# Power_Supply.net
KiCad netlist of a schematic drawn in Altium Designer
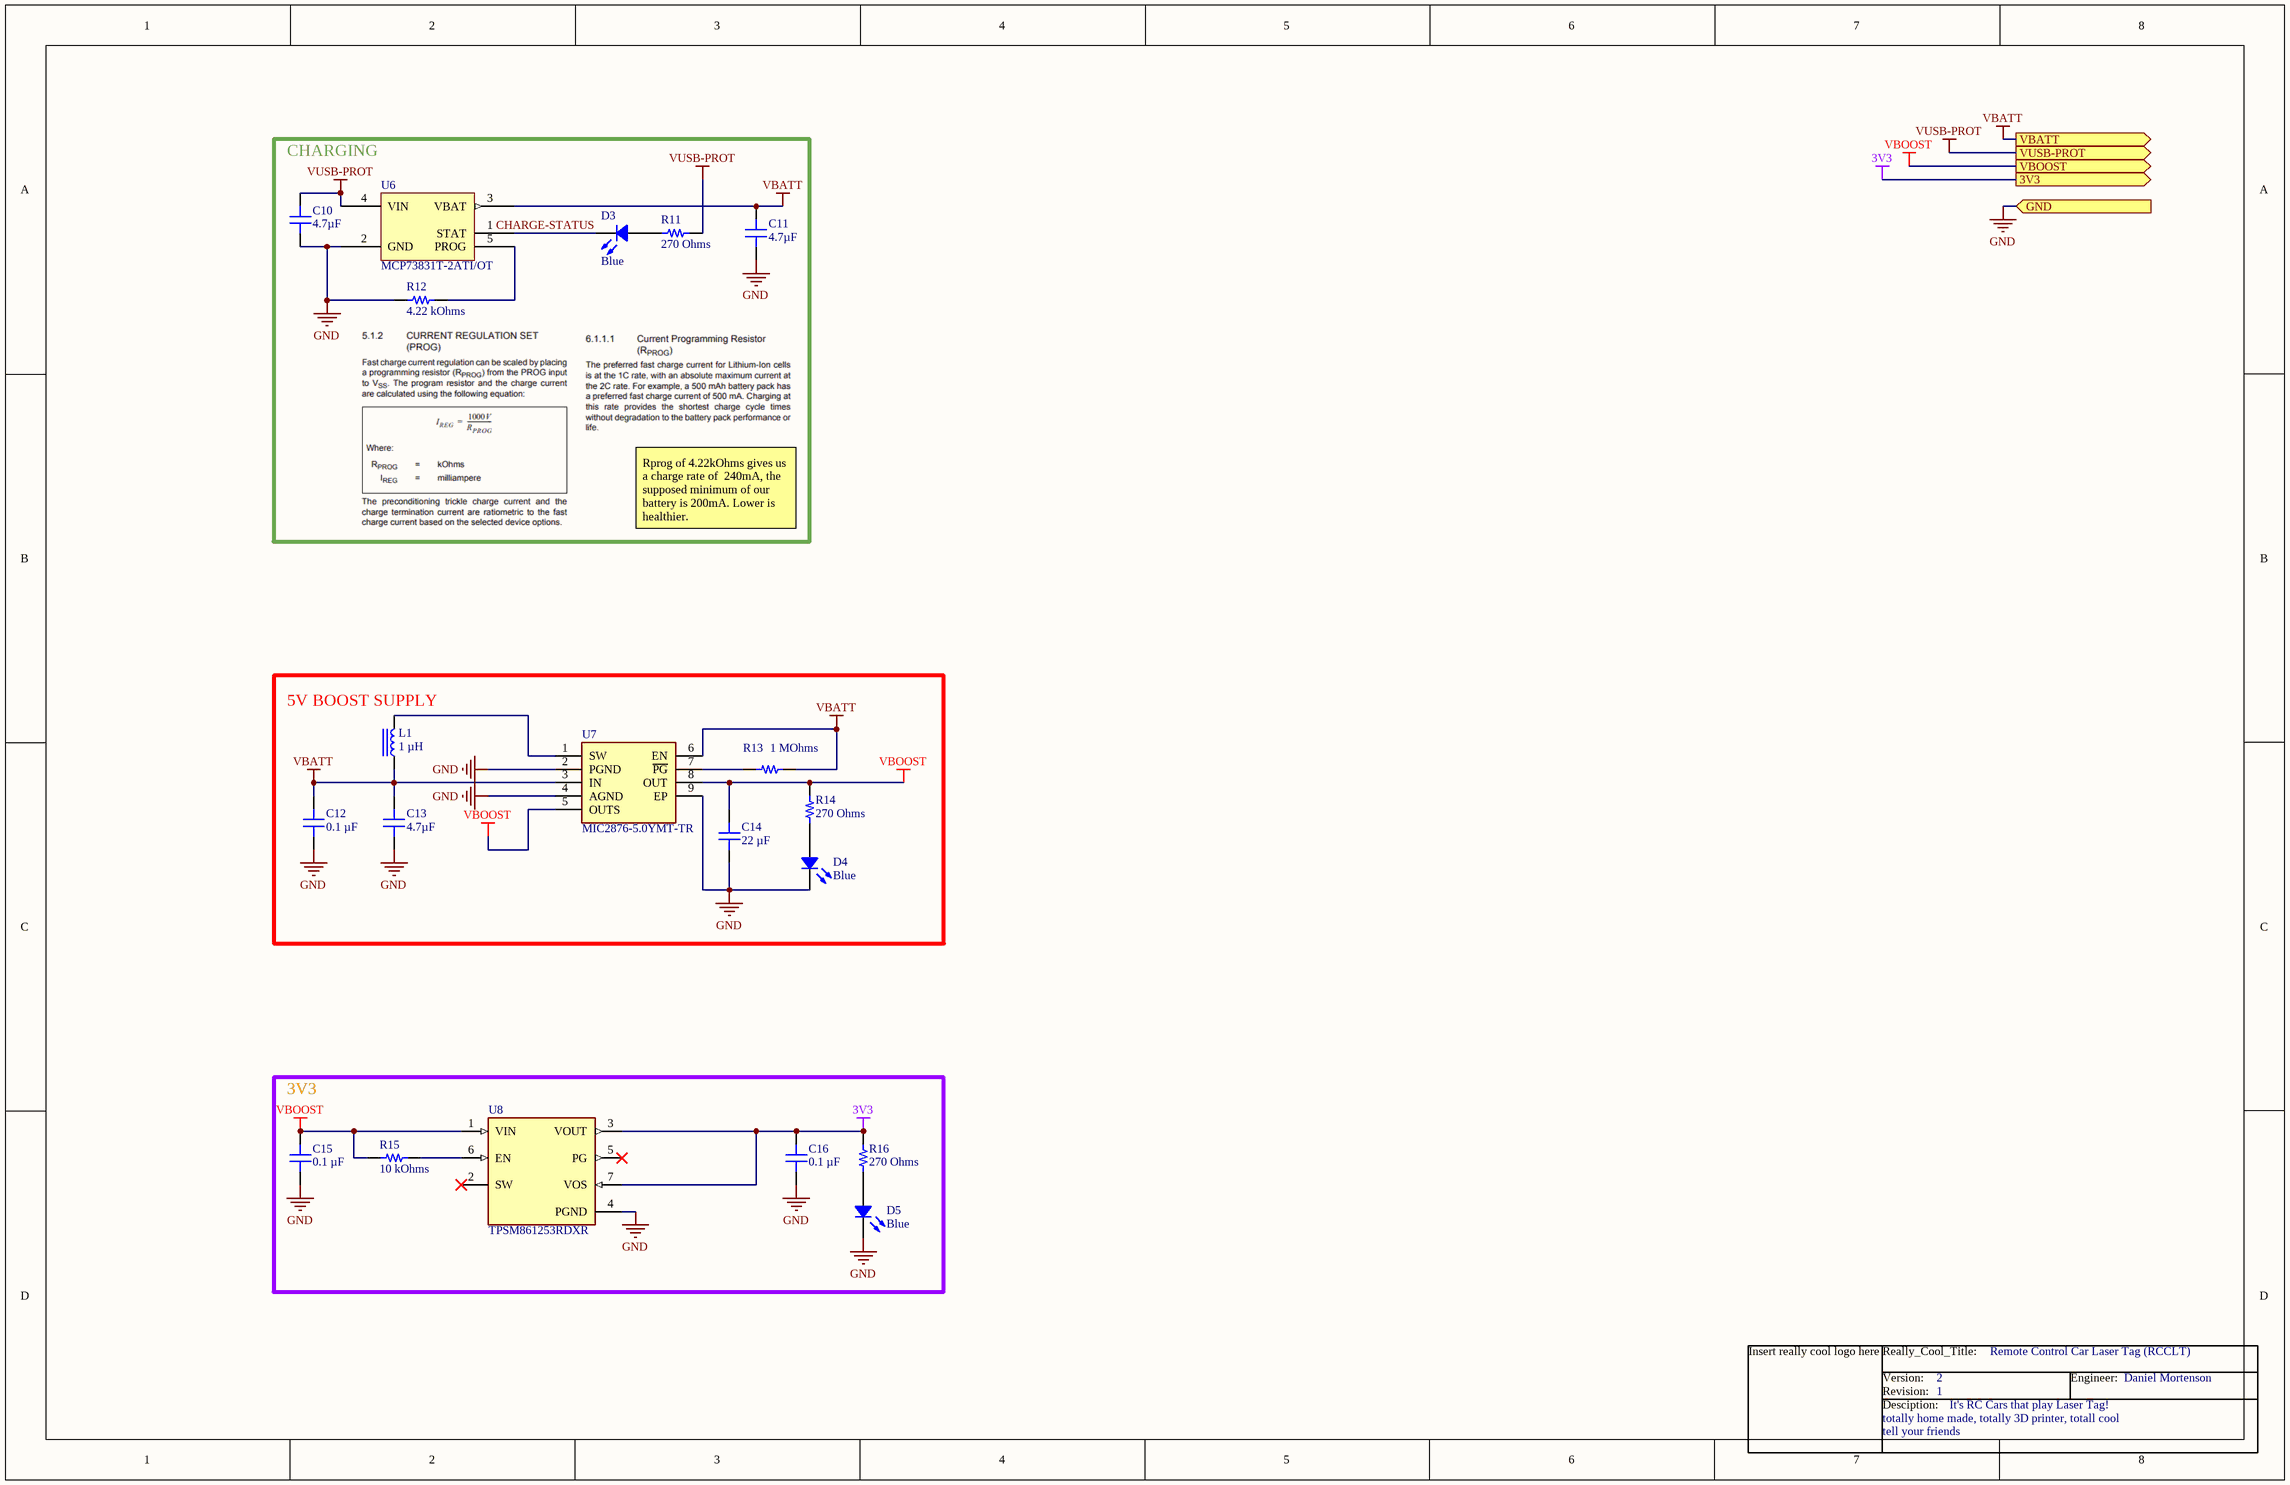
[diagram p0: Power_Supply.SchDoc]

(export (version "E")
  (design (tool "Eeschema 10.0.6"))
  (components
    (comp (ref "C10")
      (value "4.7µF")
      (footprint "CAP 0805_2012")
      (description "CAP CER 4.7UF 16V X7R 0805")
      (fields
        (field (name "PART NUMBER") "0805YC475KAT2A")
        (field (name "CAPACITANCE") "4.7µF")
        (field (name "MANUFACTURER") "AVX Corporation")
      )
      (libsource (lib "dblib") (part "Capacitor"))
    )
    (comp (ref "C11")
      (value "4.7µF")
      (footprint "CAP 0805_2012")
      (description "CAP CER 4.7UF 16V X7R 0805")
      (fields
        (field (name "PART NUMBER") "0805YC475KAT2A")
        (field (name "CAPACITANCE") "4.7µF")
        (field (name "MANUFACTURER") "AVX Corporation")
      )
      (libsource (lib "dblib") (part "Capacitor"))
    )
    (comp (ref "C12")
      (value "0.1 µF")
      (footprint "CAP 0805_2012")
      (description "CAP CER 0.1UF 25V X7R 0805")
      (fields
        (field (name "PART NUMBER") "0805B104K250CT")
        (field (name "CAPACITANCE") "0.1 µF")
        (field (name "MANUFACTURER") "Walsin Technology Corporation")
      )
      (libsource (lib "dblib") (part "Capacitor"))
    )
    (comp (ref "C13")
      (value "4.7µF")
      (footprint "CAP 0805_2012")
      (description "CAP CER 4.7UF 16V X7R 0805")
      (fields
        (field (name "PART NUMBER") "0805YC475KAT2A")
        (field (name "CAPACITANCE") "4.7µF")
        (field (name "MANUFACTURER") "AVX Corporation")
      )
      (libsource (lib "dblib") (part "Capacitor"))
    )
    (comp (ref "C14")
      (value "22 µF")
      (footprint "CAP 0805_2012")
      (description "CAP CER 22UF 6.3V X5R 0805")
      (fields
        (field (name "PART NUMBER") "CL21A226KQQNNNE")
        (field (name "CAPACITANCE") "22 µF")
        (field (name "MANUFACTURER") "Samsung Electro-Mechanics")
      )
      (libsource (lib "dblib") (part "Capacitor"))
    )
    (comp (ref "C15")
      (value "0.1 µF")
      (footprint "CAP 0805_2012")
      (description "CAP CER 0.1UF 25V X7R 0805")
      (fields
        (field (name "PART NUMBER") "0805B104K250CT")
        (field (name "CAPACITANCE") "0.1 µF")
        (field (name "MANUFACTURER") "Walsin Technology Corporation")
      )
      (libsource (lib "dblib") (part "Capacitor"))
    )
    (comp (ref "C16")
      (value "0.1 µF")
      (footprint "CAP 0805_2012")
      (description "CAP CER 0.1UF 25V X7R 0805")
      (fields
        (field (name "PART NUMBER") "0805B104K250CT")
        (field (name "CAPACITANCE") "0.1 µF")
        (field (name "MANUFACTURER") "Walsin Technology Corporation")
      )
      (libsource (lib "dblib") (part "Capacitor"))
    )
    (comp (ref "D3")
      (value "Blue")
      (footprint "LED 0805_2012 BLUE")
      (description "LED BLUE CLEAR 0805 SMD")
      (fields (field (name "PART NUMBER") "150080BS75000") (field (name "MANUFACTURER") "Würth Elektronik"))
      (libsource (lib "dblib") (part "LED"))
    )
    (comp (ref "D4")
      (value "Blue")
      (footprint "LED 0805_2012 BLUE")
      (description "LED BLUE CLEAR 0805 SMD")
      (fields (field (name "PART NUMBER") "150080BS75000") (field (name "MANUFACTURER") "Würth Elektronik"))
      (libsource (lib "dblib") (part "LED"))
    )
    (comp (ref "D5")
      (value "Blue")
      (footprint "LED 0805_2012 BLUE")
      (description "LED BLUE CLEAR 0805 SMD")
      (fields (field (name "PART NUMBER") "150080BS75000") (field (name "MANUFACTURER") "Würth Elektronik"))
      (libsource (lib "dblib") (part "LED"))
    )
    (comp (ref "L1")
      (value "1 µH")
      (footprint "TAIYO YUDEN MAMK2520T1R0M")
      (description "FIXED IND 1UH 2.7A 59 MOHM SMD")
      (fields (field (name "PART NUMBER") "MAMK2520T1R0M") (field (name "MANUFACTURER") "Taiyo Yuden"))
      (libsource (lib "dblib") (part "Inductor"))
    )
    (comp (ref "R11")
      (value "270 Ohms")
      (footprint "RES 0805_2012")
      (description "RES SMD 270 OHM 1% 1/8W 0805")
      (fields
        (field (name "PART NUMBER") "CRG0805F270R")
        (field (name "MANUFACTURER") "TE Connectivity Passive Product")
      )
      (libsource (lib "dblib") (part "Resistor"))
    )
    (comp (ref "R12")
      (value "4.22 kOhms")
      (footprint "RES 0805_2012")
      (description "RES SMD 4.22K OHM 0.1% 1/8W 0805")
      (fields
        (field (name "PART NUMBER") "ERA-6AEB4221V")
        (field (name "MANUFACTURER") "Panasonic Electronic Components")
      )
      (libsource (lib "dblib") (part "Resistor"))
    )
    (comp (ref "R13")
      (value "1 MOhms")
      (footprint "RES 0805_2012")
      (description "RES 1M OHM 0.1% 1/8W 0805")
      (fields
        (field (name "PART NUMBER") "ERA-6AEB105V")
        (field (name "MANUFACTURER") "Panasonic Electronic Components")
      )
      (libsource (lib "dblib") (part "Resistor"))
    )
    (comp (ref "R14")
      (value "270 Ohms")
      (footprint "RES 0805_2012")
      (description "RES SMD 270 OHM 1% 1/8W 0805")
      (fields
        (field (name "PART NUMBER") "CRG0805F270R")
        (field (name "MANUFACTURER") "TE Connectivity Passive Product")
      )
      (libsource (lib "dblib") (part "Resistor"))
    )
    (comp (ref "R15")
      (value "10 kOhms")
      (footprint "RES 0805_2012")
      (description "RES SMD 10K OHM 1% 1/8W 0805")
      (fields (field (name "PART NUMBER") "CRCW080510K0FKEA") (field (name "MANUFACTURER") "Vishay Dale"))
      (libsource (lib "dblib") (part "Resistor"))
    )
    (comp (ref "R16")
      (value "270 Ohms")
      (footprint "RES 0805_2012")
      (description "RES SMD 270 OHM 1% 1/8W 0805")
      (fields
        (field (name "PART NUMBER") "CRG0805F270R")
        (field (name "MANUFACTURER") "TE Connectivity Passive Product")
      )
      (libsource (lib "dblib") (part "Resistor"))
    )
    (comp (ref "U6")
      (value "MCP73831T-2ATI/OT")
      (footprint "MICROCHIP SOT-23-5 OT")
      (description "IC CONTROLLR LI-ION 4.2V SOT23-5")
      (fields (field (name "MANUFACTURER") "Microchip Technology"))
      (libsource (lib "dblib") (part "MICROCHIP MCP73831"))
    )
    (comp (ref "U7")
      (value "MIC2876-5.0YMT-TR")
      (footprint "SamacSys:MIC287650YMTTR")
      (description "Integrated Circuit")
      (fields (field (name "MOUSER PART NUMBER") "998-MIC2876-50YMTTR"))
      (libsource (lib "*") (part "MIC2876-5.0YMT-TR"))
    )
    (comp (ref "U8")
      (value "TPSM861253RDXR")
      (footprint "VREG_TPSM861253RDXR")
      (description "3V to 17V input voltage, 3.3V, 1A output synchronous buck module in QFN package")
      (fields (field (name "MF") "Texas Instruments"))
      (libsource (lib "TPSM861253RDXR") (part "TPSM861253RDXR"))
    )
  )
  (nets
    (net (code "1") (name "/CHARGE-STATUS") (class "Default")
      (node (ref "D3") (pin "2") (pinfunction "2_2") (pintype "passive"))
      (node (ref "U6") (pin "1") (pinfunction "STAT_1") (pintype "passive"))
    )
    (net (code "2") (name "3V3") (class "Default")
      (node (ref "C16") (pin "2") (pinfunction "2_2") (pintype "passive"))
      (node (ref "R16") (pin "1") (pinfunction "1_1") (pintype "passive"))
      (node (ref "U8") (pin "3") (pinfunction "VOUT_3") (pintype "output"))
      (node (ref "U8") (pin "7") (pinfunction "VOS_7") (pintype "input"))
    )
    (net (code "3") (name "GND") (class "Default")
      (node (ref "C10") (pin "2") (pinfunction "2_2") (pintype "passive"))
      (node (ref "C11") (pin "2") (pinfunction "2_2") (pintype "passive"))
      (node (ref "C12") (pin "1") (pinfunction "1_1") (pintype "passive"))
      (node (ref "C13") (pin "1") (pinfunction "1_1") (pintype "passive"))
      (node (ref "C14") (pin "1") (pinfunction "1_1") (pintype "passive"))
      (node (ref "C15") (pin "1") (pinfunction "1_1") (pintype "passive"))
      (node (ref "C16") (pin "1") (pinfunction "1_1") (pintype "passive"))
      (node (ref "D4") (pin "2") (pinfunction "2_2") (pintype "passive"))
      (node (ref "D5") (pin "2") (pinfunction "2_2") (pintype "passive"))
      (node (ref "R12") (pin "1") (pinfunction "1_1") (pintype "passive"))
      (node (ref "U6") (pin "2") (pinfunction "GND_2") (pintype "passive"))
      (node (ref "U7") (pin "2") (pinfunction "PGND_2") (pintype "passive"))
      (node (ref "U7") (pin "4") (pinfunction "AGND_4") (pintype "passive"))
      (node (ref "U7") (pin "9") (pinfunction "EP_9") (pintype "passive"))
      (node (ref "U8") (pin "4") (pinfunction "PGND_4") (pintype "passive"))
    )
    (net (code "4") (name "Net-(D3-Pad1)") (class "Default")
      (node (ref "D3") (pin "1") (pinfunction "1_1") (pintype "passive"))
      (node (ref "R11") (pin "2") (pinfunction "2_2") (pintype "passive"))
    )
    (net (code "5") (name "Net-(D4-Pad1)") (class "Default")
      (node (ref "D4") (pin "1") (pinfunction "1_1") (pintype "passive"))
      (node (ref "R14") (pin "2") (pinfunction "2_2") (pintype "passive"))
    )
    (net (code "6") (name "Net-(D5-Pad1)") (class "Default")
      (node (ref "D5") (pin "1") (pinfunction "1_1") (pintype "passive"))
      (node (ref "R16") (pin "2") (pinfunction "2_2") (pintype "passive"))
    )
    (net (code "7") (name "Net-(U6-PROG)") (class "Default")
      (node (ref "R12") (pin "2") (pinfunction "2_2") (pintype "passive"))
      (node (ref "U6") (pin "5") (pinfunction "PROG_5") (pintype "passive"))
    )
    (net (code "8") (name "Net-(U7-SW)") (class "Default")
      (node (ref "L1") (pin "2") (pinfunction "2_2") (pintype "passive"))
      (node (ref "U7") (pin "1") (pinfunction "SW_1") (pintype "passive"))
    )
    (net (code "9") (name "Net-(U7-~{PG})") (class "Default")
      (node (ref "R13") (pin "1") (pinfunction "1_1") (pintype "passive"))
      (node (ref "U7") (pin "7") (pinfunction "~{PG}_7") (pintype "passive"))
    )
    (net (code "10") (name "Net-(U8-EN)") (class "Default")
      (node (ref "R15") (pin "1") (pinfunction "1_1") (pintype "passive"))
      (node (ref "U8") (pin "6") (pinfunction "EN_6") (pintype "input"))
    )
    (net (code "11") (name "VBATT") (class "Default")
      (node (ref "C11") (pin "1") (pinfunction "1_1") (pintype "passive"))
      (node (ref "C12") (pin "2") (pinfunction "2_2") (pintype "passive"))
      (node (ref "C13") (pin "2") (pinfunction "2_2") (pintype "passive"))
      (node (ref "L1") (pin "1") (pinfunction "1_1") (pintype "passive"))
      (node (ref "R13") (pin "2") (pinfunction "2_2") (pintype "passive"))
      (node (ref "U6") (pin "3") (pinfunction "VBAT_3") (pintype "output"))
      (node (ref "U7") (pin "3") (pinfunction "IN_3") (pintype "passive"))
      (node (ref "U7") (pin "6") (pinfunction "EN_6") (pintype "passive"))
    )
    (net (code "12") (name "VBOOST") (class "Default")
      (node (ref "C14") (pin "2") (pinfunction "2_2") (pintype "passive"))
      (node (ref "C15") (pin "2") (pinfunction "2_2") (pintype "passive"))
      (node (ref "R14") (pin "1") (pinfunction "1_1") (pintype "passive"))
      (node (ref "R15") (pin "2") (pinfunction "2_2") (pintype "passive"))
      (node (ref "U7") (pin "5") (pinfunction "OUTS_5") (pintype "passive"))
      (node (ref "U7") (pin "8") (pinfunction "OUT_8") (pintype "passive"))
      (node (ref "U8") (pin "1") (pinfunction "VIN_1") (pintype "input"))
    )
    (net (code "13") (name "VUSB-PROT") (class "Default")
      (node (ref "C10") (pin "1") (pinfunction "1_1") (pintype "passive"))
      (node (ref "R11") (pin "1") (pinfunction "1_1") (pintype "passive"))
      (node (ref "U6") (pin "4") (pinfunction "VIN_4") (pintype "passive"))
    )
    (net (code "14") (name "unconnected-(U8-PG-Pad5)") (class "Default")
      (node (ref "U8") (pin "5") (pinfunction "PG_5") (pintype "output+no_connect"))
    )
    (net (code "15") (name "unconnected-(U8-SW-Pad2)") (class "Default")
      (node (ref "U8") (pin "2") (pinfunction "SW_2") (pintype "passive+no_connect"))
    )
  )
)
